# superior-no-branding.net
KiCad netlist of a schematic drawn in EAGLE
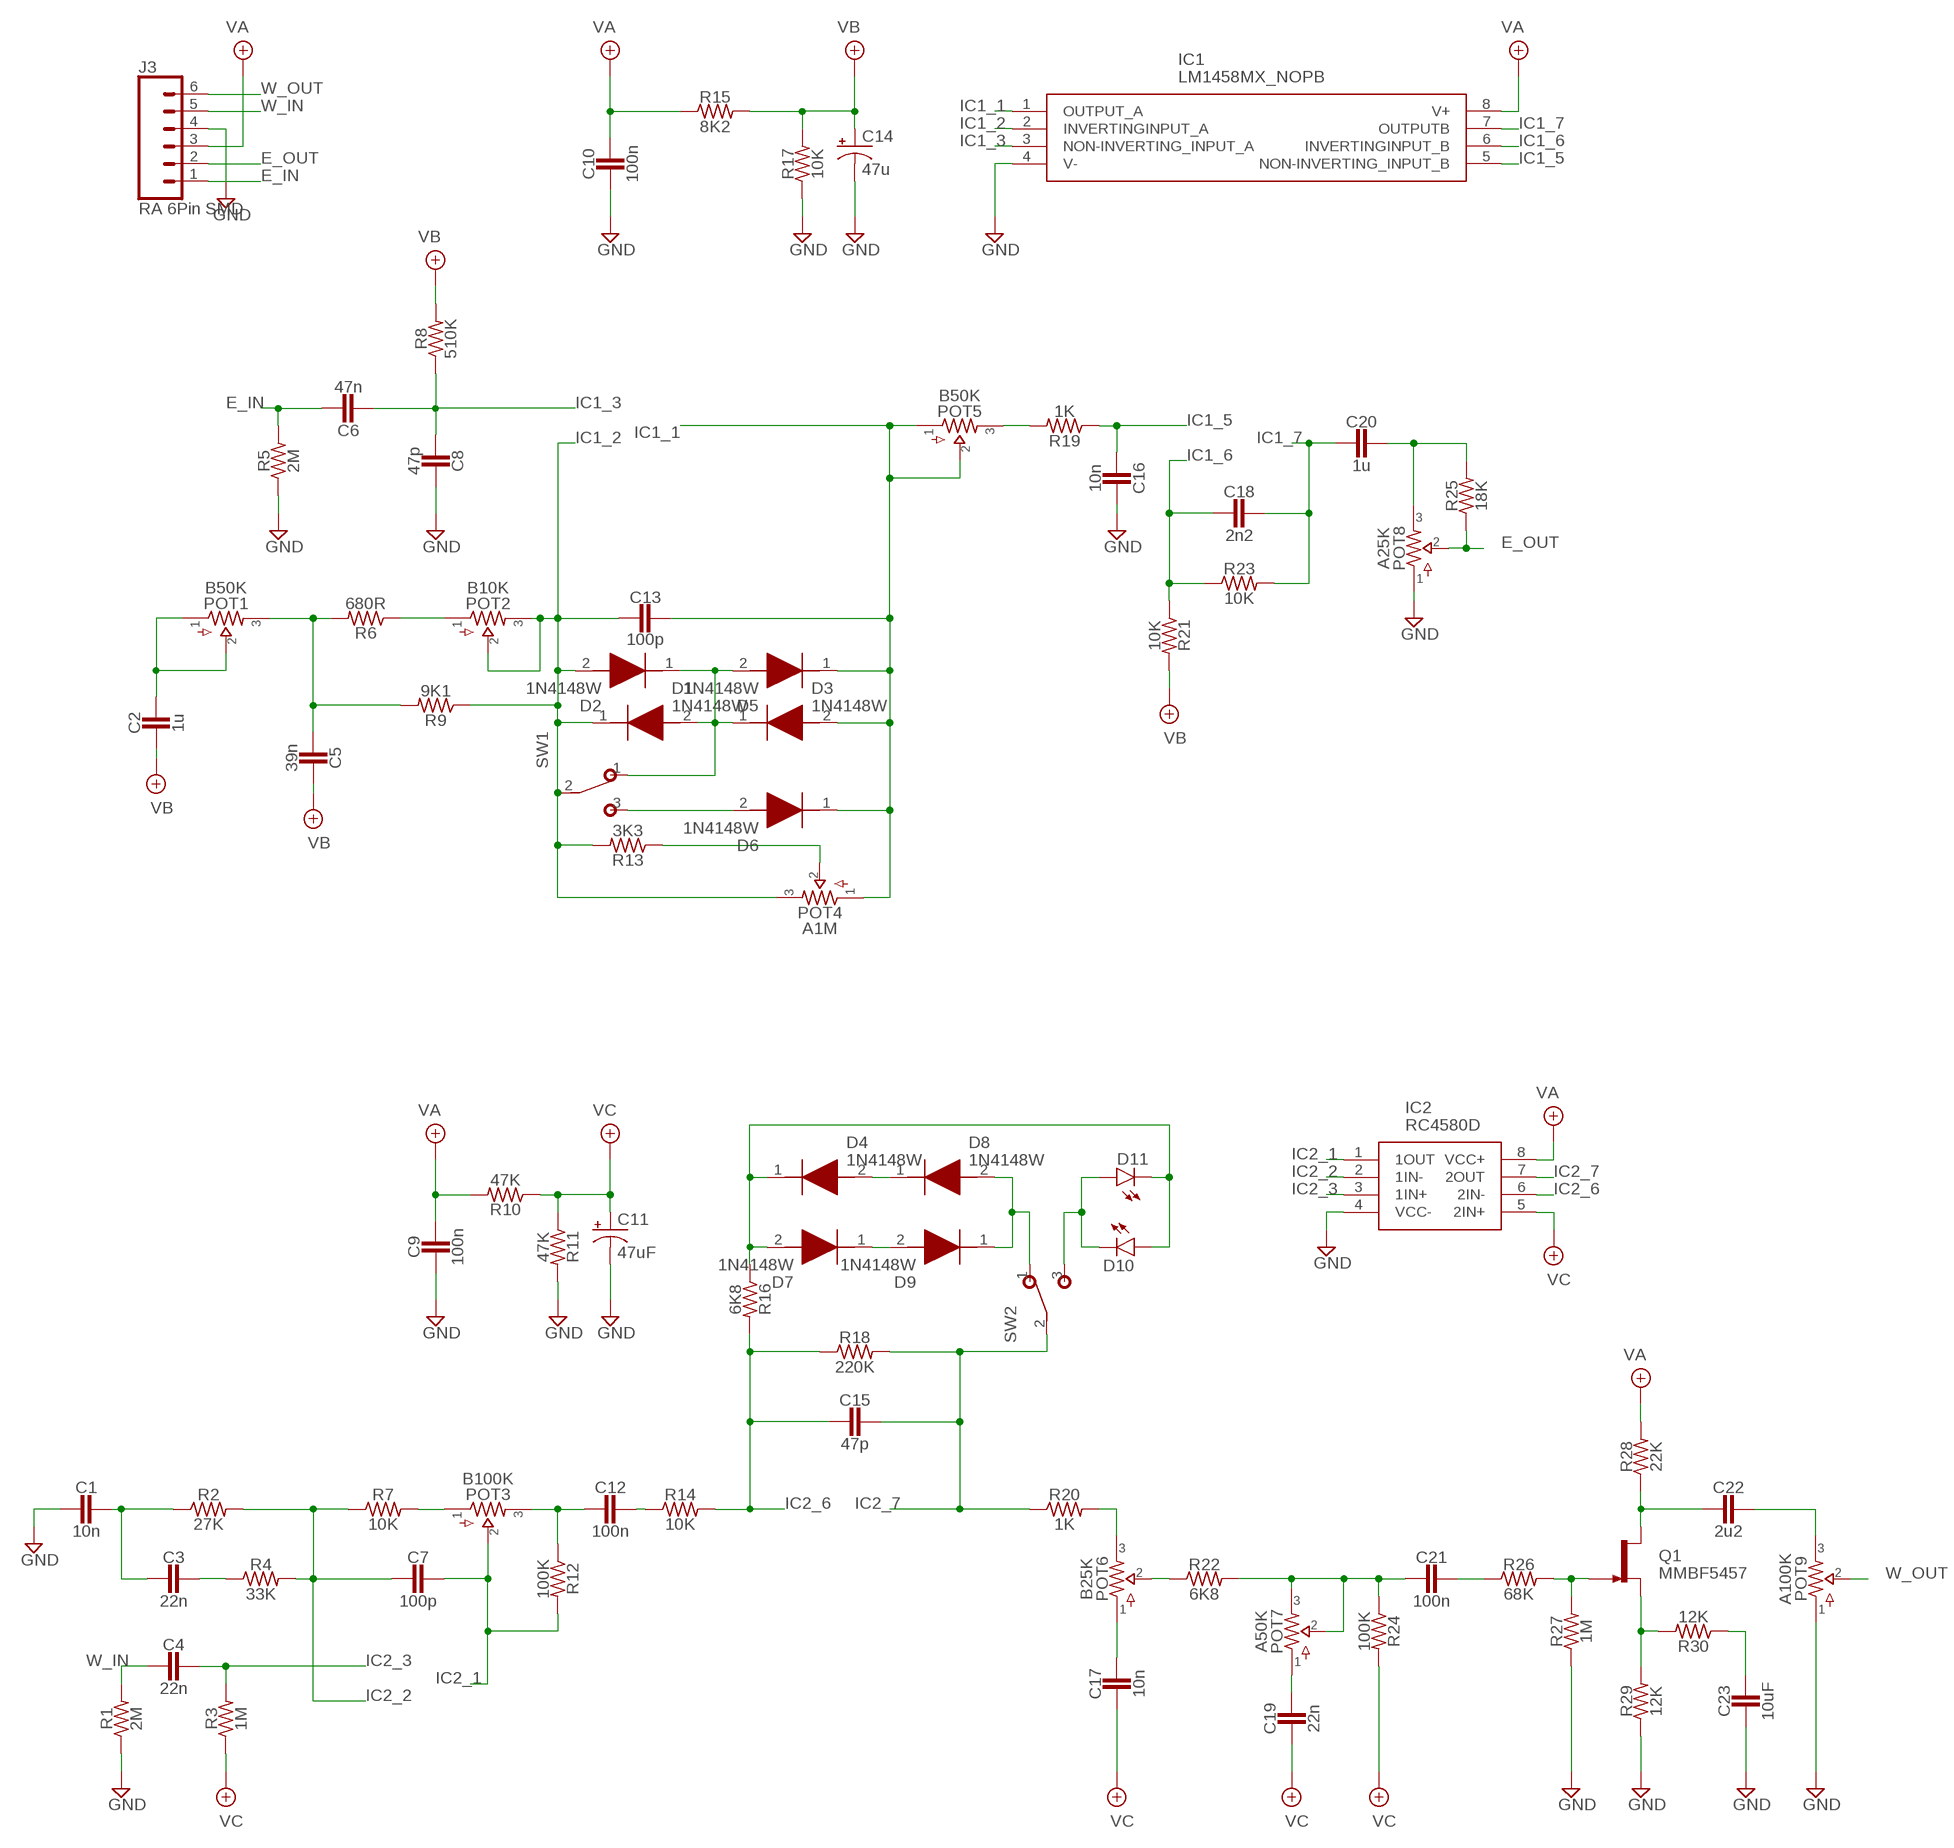
[diagram p0: schematic, sheet 1]

(export (version "E")
  (design (tool "Eeschema 10.0.6"))
  (components
    (comp (ref "C1")
      (value "10n")
      (footprint "eagle-import:0603")
      (libsource (lib "eagle-import") (part "CAP0603"))
    )
    (comp (ref "C2")
      (value "1u")
      (footprint "eagle-import:0805")
      (libsource (lib "eagle-import") (part "CAP0805"))
    )
    (comp (ref "C3")
      (value "22n")
      (footprint "eagle-import:0603")
      (libsource (lib "eagle-import") (part "CAP0603"))
    )
    (comp (ref "C4")
      (value "22n")
      (footprint "eagle-import:0805")
      (libsource (lib "eagle-import") (part "CAP0805"))
    )
    (comp (ref "C5")
      (value "39n")
      (footprint "eagle-import:0603")
      (libsource (lib "eagle-import") (part "CAP0603"))
    )
    (comp (ref "C6")
      (value "47n")
      (footprint "eagle-import:1206")
      (libsource (lib "eagle-import") (part "CAP1206"))
    )
    (comp (ref "C7")
      (value "100p")
      (footprint "eagle-import:0603")
      (libsource (lib "eagle-import") (part "CAP0603"))
    )
    (comp (ref "C8")
      (value "47p")
      (footprint "eagle-import:0603")
      (libsource (lib "eagle-import") (part "CAP0603"))
    )
    (comp (ref "C9")
      (value "100n")
      (footprint "eagle-import:0603")
      (libsource (lib "eagle-import") (part "CAP0603"))
    )
    (comp (ref "C10")
      (value "100n")
      (footprint "eagle-import:0603")
      (libsource (lib "eagle-import") (part "CAP0603"))
    )
    (comp (ref "C11")
      (value "47uF")
      (footprint "eagle-import:050_020_1")
      (libsource (lib "eagle-import") (part "0501"))
    )
    (comp (ref "C12")
      (value "100n")
      (footprint "eagle-import:1206")
      (libsource (lib "eagle-import") (part "CAP1206"))
    )
    (comp (ref "C13")
      (value "100p")
      (footprint "eagle-import:0.2_.MED")
      (libsource (lib "eagle-import") (part "CAP?.3"))
    )
    (comp (ref "C14")
      (value "47u")
      (footprint "eagle-import:050_020_1")
      (libsource (lib "eagle-import") (part "0501"))
    )
    (comp (ref "C15")
      (value "47p")
      (footprint "eagle-import:0603")
      (libsource (lib "eagle-import") (part "CAP0603"))
    )
    (comp (ref "C16")
      (value "10n")
      (footprint "eagle-import:0603")
      (libsource (lib "eagle-import") (part "CAP0603"))
    )
    (comp (ref "C17")
      (value "10n")
      (footprint "eagle-import:0603")
      (libsource (lib "eagle-import") (part "CAP0603"))
    )
    (comp (ref "C18")
      (value "2n2")
      (footprint "eagle-import:0603")
      (libsource (lib "eagle-import") (part "CAP0603"))
    )
    (comp (ref "C19")
      (value "22n")
      (footprint "eagle-import:0603")
      (libsource (lib "eagle-import") (part "CAP0603"))
    )
    (comp (ref "C20")
      (value "1u")
      (footprint "eagle-import:1206")
      (libsource (lib "eagle-import") (part "CAP1206"))
    )
    (comp (ref "C21")
      (value "100n")
      (footprint "eagle-import:1206")
      (libsource (lib "eagle-import") (part "CAP1206"))
    )
    (comp (ref "C22")
      (value "2u2")
      (footprint "eagle-import:1206")
      (libsource (lib "eagle-import") (part "CAP1206"))
    )
    (comp (ref "C23")
      (value "10uF")
      (footprint "eagle-import:1206")
      (libsource (lib "eagle-import") (part "CAP1206"))
    )
    (comp (ref "D1")
      (value "1N4148W")
      (footprint "eagle-import:SODFL3816X120N")
      (fields (field (name "MOUSER_PART_NUMBER") "637-1N4148W"))
      (libsource (lib "eagle-import") (part "1N4148W"))
    )
    (comp (ref "D2")
      (value "1N4148W")
      (footprint "eagle-import:SODFL3816X120N")
      (fields (field (name "MOUSER_PART_NUMBER") "637-1N4148W"))
      (libsource (lib "eagle-import") (part "1N4148W"))
    )
    (comp (ref "D3")
      (value "1N4148W")
      (footprint "eagle-import:SODFL3816X120N")
      (fields (field (name "MOUSER_PART_NUMBER") "637-1N4148W"))
      (libsource (lib "eagle-import") (part "1N4148W"))
    )
    (comp (ref "D4")
      (value "1N4148W")
      (footprint "eagle-import:SODFL3816X120N")
      (fields (field (name "MOUSER_PART_NUMBER") "637-1N4148W"))
      (libsource (lib "eagle-import") (part "1N4148W"))
    )
    (comp (ref "D5")
      (value "1N4148W")
      (footprint "eagle-import:SODFL3816X120N")
      (fields (field (name "MOUSER_PART_NUMBER") "637-1N4148W"))
      (libsource (lib "eagle-import") (part "1N4148W"))
    )
    (comp (ref "D6")
      (value "1N4148W")
      (footprint "eagle-import:SODFL3816X120N")
      (fields (field (name "MOUSER_PART_NUMBER") "637-1N4148W"))
      (libsource (lib "eagle-import") (part "1N4148W"))
    )
    (comp (ref "D7")
      (value "1N4148W")
      (footprint "eagle-import:SODFL3816X120N")
      (fields (field (name "MOUSER_PART_NUMBER") "637-1N4148W"))
      (libsource (lib "eagle-import") (part "1N4148W"))
    )
    (comp (ref "D8")
      (value "1N4148W")
      (footprint "eagle-import:SODFL3816X120N")
      (fields (field (name "MOUSER_PART_NUMBER") "637-1N4148W"))
      (libsource (lib "eagle-import") (part "1N4148W"))
    )
    (comp (ref "D9")
      (value "1N4148W")
      (footprint "eagle-import:SODFL3816X120N")
      (fields (field (name "MOUSER_PART_NUMBER") "637-1N4148W"))
      (libsource (lib "eagle-import") (part "1N4148W"))
    )
    (comp (ref "D10")
      (value "LED3MM")
      (footprint "eagle-import:LED3MM")
      (libsource (lib "eagle-import") (part "LED3MM"))
    )
    (comp (ref "D11")
      (value "LED3MM")
      (footprint "eagle-import:LED3MM")
      (libsource (lib "eagle-import") (part "LED3MM"))
    )
    (comp (ref "IC1")
      (value "LM1458MX_NOPB")
      (footprint "eagle-import:SOIC127P600X175-8N")
      (fields
        (field (name "MANUFACTURER_PART_NUMBER") "LM1458MX/NOPB")
        (field (name "MOUSER_PART_NUMBER") "926-LM1458MX/NOPB")
      )
      (libsource (lib "eagle-import") (part "LM1458MX_NOPB"))
    )
    (comp (ref "IC2")
      (value "RC4580D")
      (footprint "eagle-import:SOIC127P600X175-8N")
      (fields
        (field (name "MANUFACTURER_PART_NUMBER") "NE5532DR")
        (field (name "MOUSER_PART_NUMBER") "595-NE5532DR")
      )
      (libsource (lib "eagle-import") (part "NE5532DR"))
    )
    (comp (ref "J3")
      (value "RA 6Pin SMD")
      (footprint "eagle-import:1X06")
      (libsource (lib "eagle-import") (part "CONN_06SILK_FEMALE_PTH"))
    )
    (comp (ref "POT1")
      (value "B50K")
      (footprint "eagle-import:16MM_B.MOUNT")
      (libsource (lib "eagle-import") (part "16MM.1"))
    )
    (comp (ref "POT2")
      (value "B10K")
      (footprint "eagle-import:TRIM1")
      (libsource (lib "eagle-import") (part "TRIMMER"))
    )
    (comp (ref "POT3")
      (value "B100K")
      (footprint "eagle-import:16MM_B.MOUNT")
      (libsource (lib "eagle-import") (part "16MM.1"))
    )
    (comp (ref "POT4")
      (value "A1M")
      (footprint "eagle-import:16MM_B.MOUNT")
      (libsource (lib "eagle-import") (part "16MM.1"))
    )
    (comp (ref "POT5")
      (value "B50K")
      (footprint "eagle-import:16MM_B.MOUNT")
      (libsource (lib "eagle-import") (part "16MM.1"))
    )
    (comp (ref "POT6")
      (value "B25K")
      (footprint "eagle-import:16MM_B.MOUNT")
      (libsource (lib "eagle-import") (part "16MM.1"))
    )
    (comp (ref "POT7")
      (value "A50K")
      (footprint "eagle-import:16MM_B.MOUNT")
      (libsource (lib "eagle-import") (part "16MM.1"))
    )
    (comp (ref "POT8")
      (value "A25K")
      (footprint "eagle-import:16MM_B.MOUNT")
      (libsource (lib "eagle-import") (part "16MM.1"))
    )
    (comp (ref "POT9")
      (value "A100K")
      (footprint "eagle-import:16MM_B.MOUNT")
      (libsource (lib "eagle-import") (part "16MM.1"))
    )
    (comp (ref "Q1")
      (value "MMBF5457")
      (footprint "eagle-import:SOT23-DGS")
      (libsource (lib "eagle-import") (part "JFET"))
    )
    (comp (ref "R1")
      (value "2M")
      (footprint "eagle-import:0603")
      (libsource (lib "eagle-import") (part "RESISTOR0603"))
    )
    (comp (ref "R2")
      (value "27K")
      (footprint "eagle-import:0603")
      (libsource (lib "eagle-import") (part "RESISTOR0603"))
    )
    (comp (ref "R3")
      (value "1M")
      (footprint "eagle-import:0603")
      (libsource (lib "eagle-import") (part "RESISTOR0603"))
    )
    (comp (ref "R4")
      (value "33K")
      (footprint "eagle-import:0603")
      (libsource (lib "eagle-import") (part "RESISTOR0603"))
    )
    (comp (ref "R5")
      (value "2M")
      (footprint "eagle-import:0603")
      (libsource (lib "eagle-import") (part "RESISTOR0603"))
    )
    (comp (ref "R6")
      (value "680R")
      (footprint "eagle-import:0603")
      (libsource (lib "eagle-import") (part "RESISTOR0603"))
    )
    (comp (ref "R7")
      (value "10K")
      (footprint "eagle-import:0603")
      (libsource (lib "eagle-import") (part "RESISTOR0603"))
    )
    (comp (ref "R8")
      (value "510K")
      (footprint "eagle-import:0603")
      (libsource (lib "eagle-import") (part "RESISTOR0603"))
    )
    (comp (ref "R9")
      (value "9K1")
      (footprint "eagle-import:0603")
      (libsource (lib "eagle-import") (part "RESISTOR0603"))
    )
    (comp (ref "R10")
      (value "47K")
      (footprint "eagle-import:0603")
      (libsource (lib "eagle-import") (part "RESISTOR0603"))
    )
    (comp (ref "R11")
      (value "47K")
      (footprint "eagle-import:0603")
      (libsource (lib "eagle-import") (part "RESISTOR0603"))
    )
    (comp (ref "R12")
      (value "100K")
      (footprint "eagle-import:0603")
      (libsource (lib "eagle-import") (part "RESISTOR0603"))
    )
    (comp (ref "R13")
      (value "3K3")
      (footprint "eagle-import:0603")
      (libsource (lib "eagle-import") (part "RESISTOR0603"))
    )
    (comp (ref "R14")
      (value "10K")
      (footprint "eagle-import:0603")
      (libsource (lib "eagle-import") (part "RESISTOR0603"))
    )
    (comp (ref "R15")
      (value "8K2")
      (footprint "eagle-import:0603")
      (libsource (lib "eagle-import") (part "RESISTOR0603"))
    )
    (comp (ref "R16")
      (value "6K8")
      (footprint "eagle-import:0603")
      (libsource (lib "eagle-import") (part "RESISTOR0603"))
    )
    (comp (ref "R17")
      (value "10K")
      (footprint "eagle-import:0603")
      (libsource (lib "eagle-import") (part "RESISTOR0603"))
    )
    (comp (ref "R18")
      (value "220K")
      (footprint "eagle-import:0603")
      (libsource (lib "eagle-import") (part "RESISTOR0603"))
    )
    (comp (ref "R19")
      (value "1K")
      (footprint "eagle-import:0603")
      (libsource (lib "eagle-import") (part "RESISTOR0603"))
    )
    (comp (ref "R20")
      (value "1K")
      (footprint "eagle-import:0603")
      (libsource (lib "eagle-import") (part "RESISTOR0603"))
    )
    (comp (ref "R21")
      (value "10K")
      (footprint "eagle-import:0603")
      (libsource (lib "eagle-import") (part "RESISTOR0603"))
    )
    (comp (ref "R22")
      (value "6K8")
      (footprint "eagle-import:0603")
      (libsource (lib "eagle-import") (part "RESISTOR0603"))
    )
    (comp (ref "R23")
      (value "10K")
      (footprint "eagle-import:0603")
      (libsource (lib "eagle-import") (part "RESISTOR0603"))
    )
    (comp (ref "R24")
      (value "100K")
      (footprint "eagle-import:0603")
      (libsource (lib "eagle-import") (part "RESISTOR0603"))
    )
    (comp (ref "R25")
      (value "18K")
      (footprint "eagle-import:0603")
      (libsource (lib "eagle-import") (part "RESISTOR0603"))
    )
    (comp (ref "R26")
      (value "68K")
      (footprint "eagle-import:0603")
      (libsource (lib "eagle-import") (part "RESISTOR0603"))
    )
    (comp (ref "R27")
      (value "1M")
      (footprint "eagle-import:0603")
      (libsource (lib "eagle-import") (part "RESISTOR0603"))
    )
    (comp (ref "R28")
      (value "22K")
      (footprint "eagle-import:0603")
      (libsource (lib "eagle-import") (part "RESISTOR0603"))
    )
    (comp (ref "R29")
      (value "12K")
      (footprint "eagle-import:0603")
      (libsource (lib "eagle-import") (part "RESISTOR0603"))
    )
    (comp (ref "R30")
      (value "12K")
      (footprint "eagle-import:0603")
      (libsource (lib "eagle-import") (part "RESISTOR0603"))
    )
    (comp (ref "SW1")
      (value "SPDT")
      (footprint "eagle-import:M9040P")
      (libsource (lib "eagle-import") (part "SPDT"))
    )
    (comp (ref "SW2")
      (value "SPDT")
      (footprint "eagle-import:M9040P")
      (libsource (lib "eagle-import") (part "SPDT"))
    )
  )
  (nets
    (net (code "1") (name "/E_IN") (class "Default")
      (node (ref "C6") (pin "1") (pinfunction "1_1") (pintype "passive"))
      (node (ref "J3") (pin "1") (pinfunction "1_1") (pintype "passive"))
      (node (ref "R5") (pin "2") (pinfunction "2_2") (pintype "passive"))
    )
    (net (code "2") (name "/E_OUT") (class "Default")
      (node (ref "J3") (pin "2") (pinfunction "2_2") (pintype "passive"))
      (node (ref "POT8") (pin "2") (pinfunction "2_2") (pintype "passive"))
      (node (ref "R25") (pin "1") (pinfunction "1_1") (pintype "passive"))
    )
    (net (code "3") (name "/IC1_1") (class "Default")
      (node (ref "C13") (pin "1") (pinfunction "1_1") (pintype "passive"))
      (node (ref "D3") (pin "2") (pinfunction "A_2") (pintype "bidirectional"))
      (node (ref "D5") (pin "1") (pinfunction "K_1") (pintype "bidirectional"))
      (node (ref "D6") (pin "1") (pinfunction "K_1") (pintype "bidirectional"))
      (node (ref "IC1") (pin "1") (pinfunction "OUTPUT_A_1") (pintype "bidirectional"))
      (node (ref "POT4") (pin "1") (pinfunction "1_1") (pintype "passive"))
      (node (ref "POT5") (pin "1") (pinfunction "1_1") (pintype "passive"))
      (node (ref "POT5") (pin "2") (pinfunction "2_2") (pintype "passive"))
    )
    (net (code "4") (name "/IC1_2") (class "Default")
      (node (ref "C13") (pin "2") (pinfunction "2_2") (pintype "passive"))
      (node (ref "D1") (pin "1") (pinfunction "K_1") (pintype "bidirectional"))
      (node (ref "D2") (pin "2") (pinfunction "A_2") (pintype "bidirectional"))
      (node (ref "IC1") (pin "2") (pinfunction "INVERTINGINPUT_A_2") (pintype "bidirectional"))
      (node (ref "POT2") (pin "2") (pinfunction "2_2") (pintype "passive"))
      (node (ref "POT2") (pin "3") (pinfunction "3_3") (pintype "passive"))
      (node (ref "POT4") (pin "3") (pinfunction "3_3") (pintype "passive"))
      (node (ref "R13") (pin "2") (pinfunction "2_2") (pintype "passive"))
      (node (ref "R9") (pin "1") (pinfunction "1_1") (pintype "passive"))
      (node (ref "SW1") (pin "2") (pinfunction "P_2") (pintype "passive"))
    )
    (net (code "5") (name "/IC1_3") (class "Default")
      (node (ref "C6") (pin "2") (pinfunction "2_2") (pintype "passive"))
      (node (ref "C8") (pin "2") (pinfunction "2_2") (pintype "passive"))
      (node (ref "IC1") (pin "3") (pinfunction "NON-INVERTING_INPUT_A_3") (pintype "bidirectional"))
      (node (ref "R8") (pin "1") (pinfunction "1_1") (pintype "passive"))
    )
    (net (code "6") (name "/IC1_5") (class "Default")
      (node (ref "C16") (pin "2") (pinfunction "2_2") (pintype "passive"))
      (node (ref "IC1") (pin "5") (pinfunction "NON-INVERTING_INPUT_B_5") (pintype "bidirectional"))
      (node (ref "R19") (pin "1") (pinfunction "1_1") (pintype "passive"))
    )
    (net (code "7") (name "/IC1_6") (class "Default")
      (node (ref "C18") (pin "2") (pinfunction "2_2") (pintype "passive"))
      (node (ref "IC1") (pin "6") (pinfunction "INVERTINGINPUT_B_6") (pintype "bidirectional"))
      (node (ref "R21") (pin "1") (pinfunction "1_1") (pintype "passive"))
      (node (ref "R23") (pin "1") (pinfunction "1_1") (pintype "passive"))
    )
    (net (code "8") (name "/IC1_7") (class "Default")
      (node (ref "C18") (pin "1") (pinfunction "1_1") (pintype "passive"))
      (node (ref "C20") (pin "2") (pinfunction "2_2") (pintype "passive"))
      (node (ref "IC1") (pin "7") (pinfunction "OUTPUTB_7") (pintype "bidirectional"))
      (node (ref "R23") (pin "2") (pinfunction "2_2") (pintype "passive"))
    )
    (net (code "9") (name "/IC2_1") (class "Default")
      (node (ref "C7") (pin "1") (pinfunction "1_1") (pintype "passive"))
      (node (ref "IC2") (pin "1") (pinfunction "1OUT_1") (pintype "bidirectional"))
      (node (ref "POT3") (pin "2") (pinfunction "2_2") (pintype "passive"))
      (node (ref "R12") (pin "2") (pinfunction "2_2") (pintype "passive"))
    )
    (net (code "10") (name "/IC2_2") (class "Default")
      (node (ref "C7") (pin "2") (pinfunction "2_2") (pintype "passive"))
      (node (ref "IC2") (pin "2") (pinfunction "1IN-_2") (pintype "bidirectional"))
      (node (ref "R2") (pin "2") (pinfunction "2_2") (pintype "passive"))
      (node (ref "R4") (pin "2") (pinfunction "2_2") (pintype "passive"))
      (node (ref "R7") (pin "1") (pinfunction "1_1") (pintype "passive"))
    )
    (net (code "11") (name "/IC2_3") (class "Default")
      (node (ref "C4") (pin "1") (pinfunction "1_1") (pintype "passive"))
      (node (ref "IC2") (pin "3") (pinfunction "1IN+_3") (pintype "bidirectional"))
      (node (ref "R3") (pin "2") (pinfunction "2_2") (pintype "passive"))
    )
    (net (code "12") (name "/IC2_6") (class "Default")
      (node (ref "C15") (pin "2") (pinfunction "2_2") (pintype "passive"))
      (node (ref "IC2") (pin "6") (pinfunction "2IN-_6") (pintype "bidirectional"))
      (node (ref "R14") (pin "2") (pinfunction "2_2") (pintype "passive"))
      (node (ref "R16") (pin "2") (pinfunction "2_2") (pintype "passive"))
      (node (ref "R18") (pin "1") (pinfunction "1_1") (pintype "passive"))
    )
    (net (code "13") (name "/IC2_7") (class "Default")
      (node (ref "C15") (pin "1") (pinfunction "1_1") (pintype "passive"))
      (node (ref "IC2") (pin "7") (pinfunction "2OUT_7") (pintype "bidirectional"))
      (node (ref "R18") (pin "2") (pinfunction "2_2") (pintype "passive"))
      (node (ref "R20") (pin "1") (pinfunction "1_1") (pintype "passive"))
      (node (ref "SW2") (pin "2") (pinfunction "P_2") (pintype "passive"))
    )
    (net (code "14") (name "/W_IN") (class "Default")
      (node (ref "C4") (pin "2") (pinfunction "2_2") (pintype "passive"))
      (node (ref "J3") (pin "5") (pinfunction "5_5") (pintype "passive"))
      (node (ref "R1") (pin "2") (pinfunction "2_2") (pintype "passive"))
    )
    (net (code "15") (name "/W_OUT") (class "Default")
      (node (ref "J3") (pin "6") (pinfunction "6_6") (pintype "passive"))
      (node (ref "POT9") (pin "2") (pinfunction "2_2") (pintype "passive"))
    )
    (net (code "16") (name "GND") (class "Default")
      (node (ref "C1") (pin "2") (pinfunction "2_2") (pintype "passive"))
      (node (ref "C10") (pin "2") (pinfunction "2_2") (pintype "passive"))
      (node (ref "C11") (pin "-") (pinfunction "-_-") (pintype "passive"))
      (node (ref "C14") (pin "-") (pinfunction "-_-") (pintype "passive"))
      (node (ref "C16") (pin "1") (pinfunction "1_1") (pintype "passive"))
      (node (ref "C23") (pin "2") (pinfunction "2_2") (pintype "passive"))
      (node (ref "C8") (pin "1") (pinfunction "1_1") (pintype "passive"))
      (node (ref "C9") (pin "2") (pinfunction "2_2") (pintype "passive"))
      (node (ref "IC1") (pin "4") (pinfunction "V-_4") (pintype "bidirectional"))
      (node (ref "IC2") (pin "4") (pinfunction "VCC-_4") (pintype "bidirectional"))
      (node (ref "J3") (pin "4") (pinfunction "4_4") (pintype "passive"))
      (node (ref "POT8") (pin "1") (pinfunction "1_1") (pintype "passive"))
      (node (ref "POT9") (pin "1") (pinfunction "1_1") (pintype "passive"))
      (node (ref "R1") (pin "1") (pinfunction "1_1") (pintype "passive"))
      (node (ref "R11") (pin "2") (pinfunction "2_2") (pintype "passive"))
      (node (ref "R17") (pin "1") (pinfunction "1_1") (pintype "passive"))
      (node (ref "R27") (pin "1") (pinfunction "1_1") (pintype "passive"))
      (node (ref "R29") (pin "1") (pinfunction "1_1") (pintype "passive"))
      (node (ref "R5") (pin "1") (pinfunction "1_1") (pintype "passive"))
    )
    (net (code "17") (name "Net-(C1-Pad1)") (class "Default")
      (node (ref "C1") (pin "1") (pinfunction "1_1") (pintype "passive"))
      (node (ref "C3") (pin "2") (pinfunction "2_2") (pintype "passive"))
      (node (ref "R2") (pin "1") (pinfunction "1_1") (pintype "passive"))
    )
    (net (code "18") (name "Net-(C2-Pad1)") (class "Default")
      (node (ref "C2") (pin "1") (pinfunction "1_1") (pintype "passive"))
      (node (ref "POT1") (pin "1") (pinfunction "1_1") (pintype "passive"))
      (node (ref "POT1") (pin "2") (pinfunction "2_2") (pintype "passive"))
    )
    (net (code "19") (name "Net-(C3-Pad1)") (class "Default")
      (node (ref "C3") (pin "1") (pinfunction "1_1") (pintype "passive"))
      (node (ref "R4") (pin "1") (pinfunction "1_1") (pintype "passive"))
    )
    (net (code "20") (name "Net-(C5-Pad2)") (class "Default")
      (node (ref "C5") (pin "2") (pinfunction "2_2") (pintype "passive"))
      (node (ref "POT1") (pin "3") (pinfunction "3_3") (pintype "passive"))
      (node (ref "R6") (pin "2") (pinfunction "2_2") (pintype "passive"))
      (node (ref "R9") (pin "2") (pinfunction "2_2") (pintype "passive"))
    )
    (net (code "21") (name "Net-(C12-Pad1)") (class "Default")
      (node (ref "C12") (pin "1") (pinfunction "1_1") (pintype "passive"))
      (node (ref "R14") (pin "1") (pinfunction "1_1") (pintype "passive"))
    )
    (net (code "22") (name "Net-(C12-Pad2)") (class "Default")
      (node (ref "C12") (pin "2") (pinfunction "2_2") (pintype "passive"))
      (node (ref "POT3") (pin "3") (pinfunction "3_3") (pintype "passive"))
      (node (ref "R12") (pin "1") (pinfunction "1_1") (pintype "passive"))
    )
    (net (code "23") (name "Net-(C17-Pad1)") (class "Default")
      (node (ref "C17") (pin "1") (pinfunction "1_1") (pintype "passive"))
      (node (ref "POT6") (pin "1") (pinfunction "1_1") (pintype "passive"))
    )
    (net (code "24") (name "Net-(C19-Pad1)") (class "Default")
      (node (ref "C19") (pin "1") (pinfunction "1_1") (pintype "passive"))
      (node (ref "POT7") (pin "1") (pinfunction "1_1") (pintype "passive"))
    )
    (net (code "25") (name "Net-(C20-Pad1)") (class "Default")
      (node (ref "C20") (pin "1") (pinfunction "1_1") (pintype "passive"))
      (node (ref "POT8") (pin "3") (pinfunction "3_3") (pintype "passive"))
      (node (ref "R25") (pin "2") (pinfunction "2_2") (pintype "passive"))
    )
    (net (code "26") (name "Net-(C21-Pad1)") (class "Default")
      (node (ref "C21") (pin "1") (pinfunction "1_1") (pintype "passive"))
      (node (ref "R26") (pin "1") (pinfunction "1_1") (pintype "passive"))
    )
    (net (code "27") (name "Net-(C21-Pad2)") (class "Default")
      (node (ref "C21") (pin "2") (pinfunction "2_2") (pintype "passive"))
      (node (ref "POT7") (pin "2") (pinfunction "2_2") (pintype "passive"))
      (node (ref "POT7") (pin "3") (pinfunction "3_3") (pintype "passive"))
      (node (ref "R22") (pin "2") (pinfunction "2_2") (pintype "passive"))
      (node (ref "R24") (pin "1") (pinfunction "1_1") (pintype "passive"))
    )
    (net (code "28") (name "Net-(C22-Pad1)") (class "Default")
      (node (ref "C22") (pin "1") (pinfunction "1_1") (pintype "passive"))
      (node (ref "POT9") (pin "3") (pinfunction "3_3") (pintype "passive"))
    )
    (net (code "29") (name "Net-(C22-Pad2)") (class "Default")
      (node (ref "C22") (pin "2") (pinfunction "2_2") (pintype "passive"))
      (node (ref "Q1") (pin "D") (pinfunction "D_D") (pintype "passive"))
      (node (ref "R28") (pin "1") (pinfunction "1_1") (pintype "passive"))
    )
    (net (code "30") (name "Net-(C23-Pad1)") (class "Default")
      (node (ref "C23") (pin "1") (pinfunction "1_1") (pintype "passive"))
      (node (ref "R30") (pin "1") (pinfunction "1_1") (pintype "passive"))
    )
    (net (code "31") (name "Net-(D1-A)") (class "Default")
      (node (ref "D1") (pin "2") (pinfunction "A_2") (pintype "bidirectional"))
      (node (ref "D2") (pin "1") (pinfunction "K_1") (pintype "bidirectional"))
      (node (ref "D3") (pin "1") (pinfunction "K_1") (pintype "bidirectional"))
      (node (ref "D5") (pin "2") (pinfunction "A_2") (pintype "bidirectional"))
      (node (ref "SW1") (pin "1") (pinfunction "O_1") (pintype "passive"))
    )
    (net (code "32") (name "Net-(D4-A)") (class "Default")
      (node (ref "D4") (pin "2") (pinfunction "A_2") (pintype "bidirectional"))
      (node (ref "D8") (pin "1") (pinfunction "K_1") (pintype "bidirectional"))
    )
    (net (code "33") (name "Net-(D6-A)") (class "Default")
      (node (ref "D6") (pin "2") (pinfunction "A_2") (pintype "bidirectional"))
      (node (ref "SW1") (pin "3") (pinfunction "S_3") (pintype "passive"))
    )
    (net (code "34") (name "Net-(D7-K)") (class "Default")
      (node (ref "D7") (pin "1") (pinfunction "K_1") (pintype "bidirectional"))
      (node (ref "D9") (pin "2") (pinfunction "A_2") (pintype "bidirectional"))
    )
    (net (code "35") (name "Net-(D8-A)") (class "Default")
      (node (ref "D8") (pin "2") (pinfunction "A_2") (pintype "bidirectional"))
      (node (ref "D9") (pin "1") (pinfunction "K_1") (pintype "bidirectional"))
      (node (ref "SW2") (pin "1") (pinfunction "O_1") (pintype "passive"))
    )
    (net (code "36") (name "Net-(D10-C)") (class "Default")
      (node (ref "D10") (pin "K") (pinfunction "C_K") (pintype "passive"))
      (node (ref "D11") (pin "A") (pinfunction "A_A") (pintype "passive"))
      (node (ref "SW2") (pin "3") (pinfunction "S_3") (pintype "passive"))
    )
    (net (code "37") (name "Net-(D11-C)") (class "Default")
      (node (ref "D10") (pin "A") (pinfunction "A_A") (pintype "passive"))
      (node (ref "D11") (pin "K") (pinfunction "C_K") (pintype "passive"))
      (node (ref "D4") (pin "1") (pinfunction "K_1") (pintype "bidirectional"))
      (node (ref "D7") (pin "2") (pinfunction "A_2") (pintype "bidirectional"))
      (node (ref "R16") (pin "1") (pinfunction "1_1") (pintype "passive"))
    )
    (net (code "38") (name "Net-(POT2-Pad1)") (class "Default")
      (node (ref "POT2") (pin "1") (pinfunction "1_1") (pintype "passive"))
      (node (ref "R6") (pin "1") (pinfunction "1_1") (pintype "passive"))
    )
    (net (code "39") (name "Net-(POT3-Pad1)") (class "Default")
      (node (ref "POT3") (pin "1") (pinfunction "1_1") (pintype "passive"))
      (node (ref "R7") (pin "2") (pinfunction "2_2") (pintype "passive"))
    )
    (net (code "40") (name "Net-(POT4-Pad2)") (class "Default")
      (node (ref "POT4") (pin "2") (pinfunction "2_2") (pintype "passive"))
      (node (ref "R13") (pin "1") (pinfunction "1_1") (pintype "passive"))
    )
    (net (code "41") (name "Net-(POT5-Pad3)") (class "Default")
      (node (ref "POT5") (pin "3") (pinfunction "3_3") (pintype "passive"))
      (node (ref "R19") (pin "2") (pinfunction "2_2") (pintype "passive"))
    )
    (net (code "42") (name "Net-(POT6-Pad2)") (class "Default")
      (node (ref "POT6") (pin "2") (pinfunction "2_2") (pintype "passive"))
      (node (ref "R22") (pin "1") (pinfunction "1_1") (pintype "passive"))
    )
    (net (code "43") (name "Net-(POT6-Pad3)") (class "Default")
      (node (ref "POT6") (pin "3") (pinfunction "3_3") (pintype "passive"))
      (node (ref "R20") (pin "2") (pinfunction "2_2") (pintype "passive"))
    )
    (net (code "44") (name "Net-(Q1-PadG)") (class "Default")
      (node (ref "Q1") (pin "G") (pinfunction "G_G") (pintype "passive"))
      (node (ref "R26") (pin "2") (pinfunction "2_2") (pintype "passive"))
      (node (ref "R27") (pin "2") (pinfunction "2_2") (pintype "passive"))
    )
    (net (code "45") (name "Net-(Q1-PadS)") (class "Default")
      (node (ref "Q1") (pin "S") (pinfunction "S_S") (pintype "passive"))
      (node (ref "R29") (pin "2") (pinfunction "2_2") (pintype "passive"))
      (node (ref "R30") (pin "2") (pinfunction "2_2") (pintype "passive"))
    )
    (net (code "46") (name "VA") (class "Default")
      (node (ref "C10") (pin "1") (pinfunction "1_1") (pintype "passive"))
      (node (ref "C9") (pin "1") (pinfunction "1_1") (pintype "passive"))
      (node (ref "IC1") (pin "8") (pinfunction "V+_8") (pintype "bidirectional"))
      (node (ref "IC2") (pin "8") (pinfunction "VCC+_8") (pintype "bidirectional"))
      (node (ref "J3") (pin "3") (pinfunction "3_3") (pintype "passive"))
      (node (ref "R10") (pin "2") (pinfunction "2_2") (pintype "passive"))
      (node (ref "R15") (pin "1") (pinfunction "1_1") (pintype "passive"))
      (node (ref "R28") (pin "2") (pinfunction "2_2") (pintype "passive"))
    )
    (net (code "47") (name "VB") (class "Default")
      (node (ref "C14") (pin "+") (pinfunction "+_+") (pintype "passive"))
      (node (ref "C2") (pin "2") (pinfunction "2_2") (pintype "passive"))
      (node (ref "C5") (pin "1") (pinfunction "1_1") (pintype "passive"))
      (node (ref "R15") (pin "2") (pinfunction "2_2") (pintype "passive"))
      (node (ref "R17") (pin "2") (pinfunction "2_2") (pintype "passive"))
      (node (ref "R21") (pin "2") (pinfunction "2_2") (pintype "passive"))
      (node (ref "R8") (pin "2") (pinfunction "2_2") (pintype "passive"))
    )
    (net (code "48") (name "VC") (class "Default")
      (node (ref "C11") (pin "+") (pinfunction "+_+") (pintype "passive"))
      (node (ref "C17") (pin "2") (pinfunction "2_2") (pintype "passive"))
      (node (ref "C19") (pin "2") (pinfunction "2_2") (pintype "passive"))
      (node (ref "IC2") (pin "5") (pinfunction "2IN+_5") (pintype "bidirectional"))
      (node (ref "R10") (pin "1") (pinfunction "1_1") (pintype "passive"))
      (node (ref "R11") (pin "1") (pinfunction "1_1") (pintype "passive"))
      (node (ref "R24") (pin "2") (pinfunction "2_2") (pintype "passive"))
      (node (ref "R3") (pin "1") (pinfunction "1_1") (pintype "passive"))
    )
  )
)
